# object_1_milling.net
KiCad netlist of a schematic drawn in EAGLE
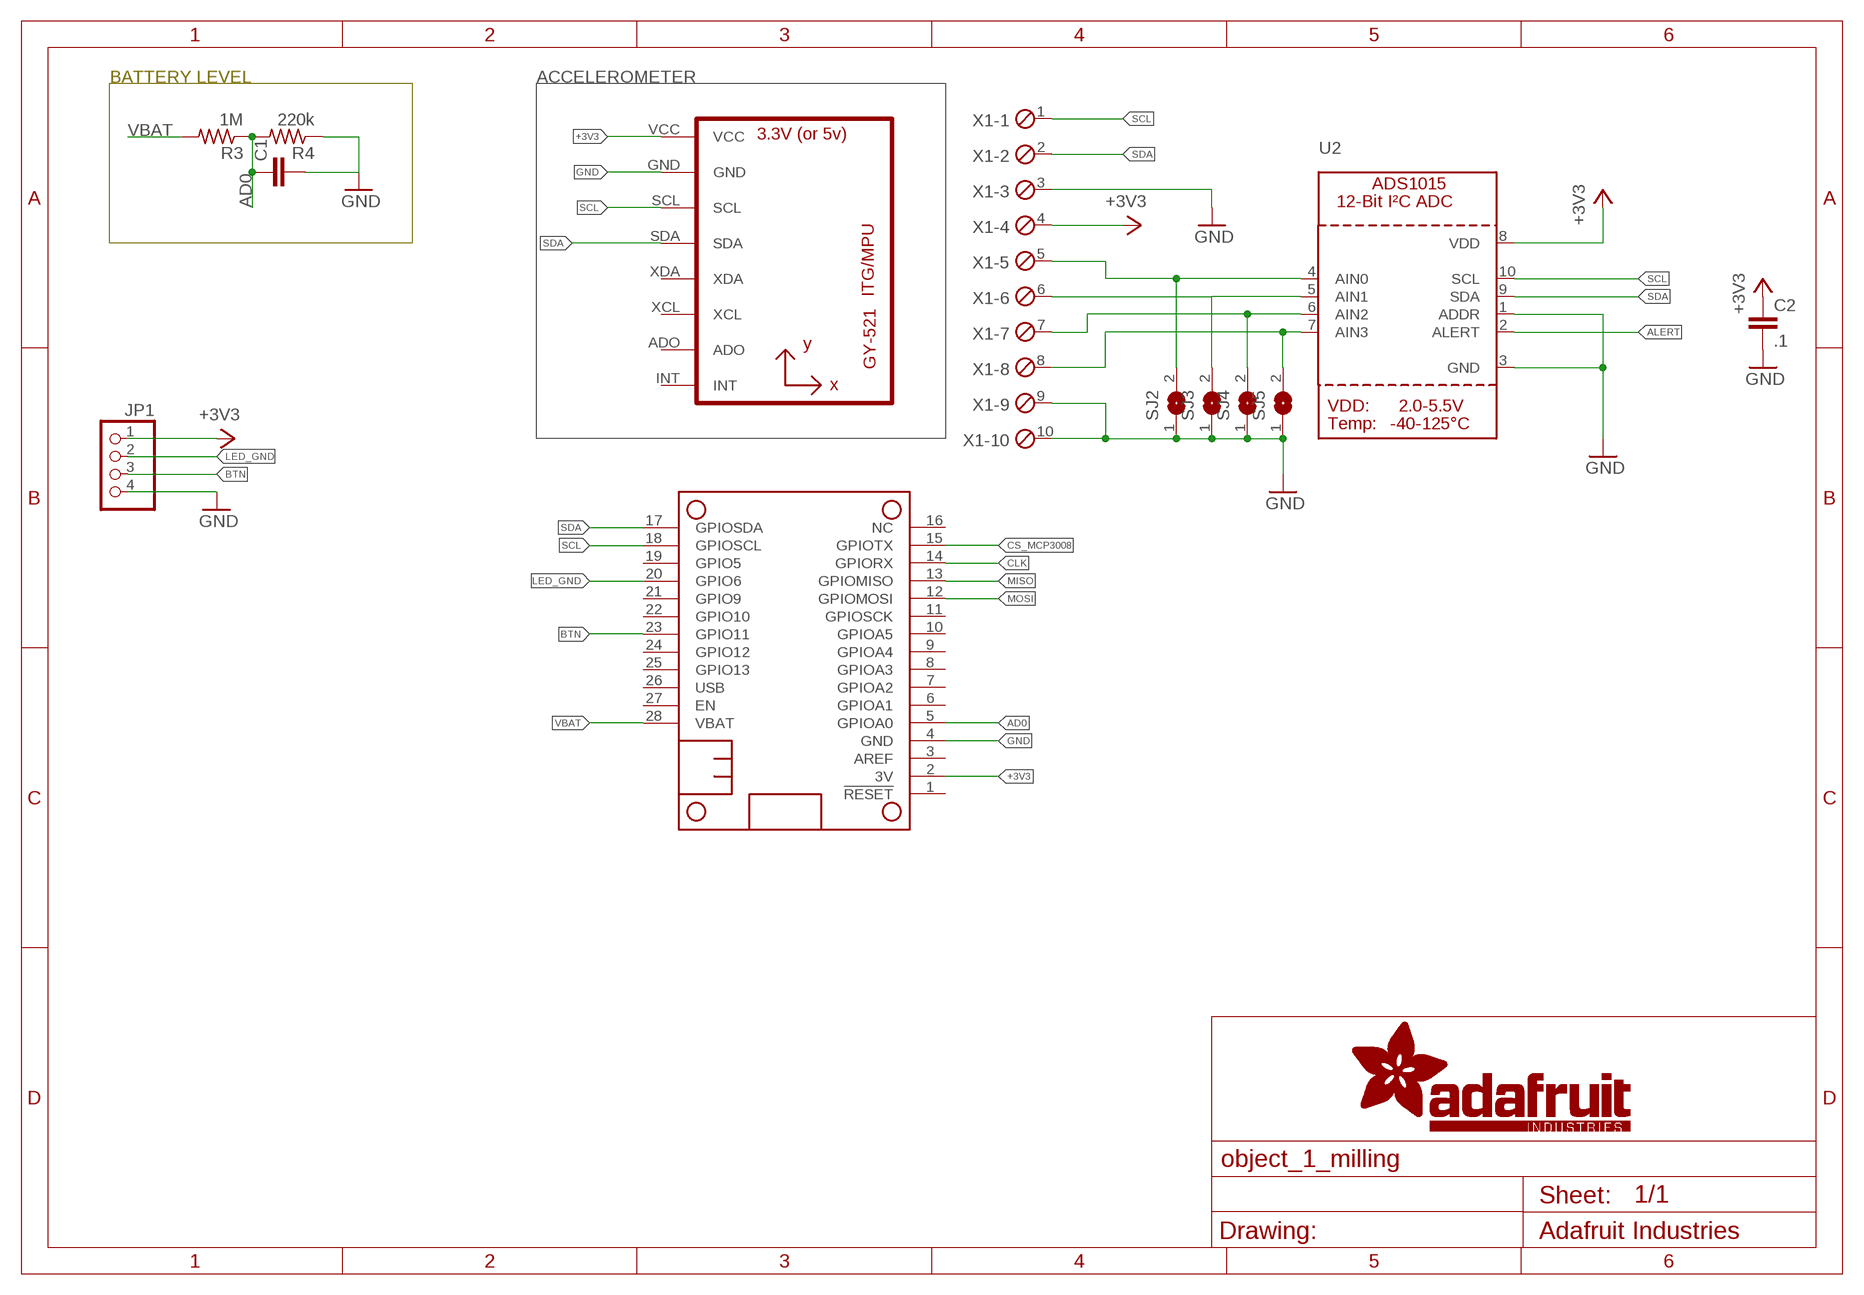
[diagram p0: schematic, sheet 1]

(export (version "E")
  (design (tool "Eeschema 10.0.6"))
  (components
    (comp (ref "C1")
      (value "C-EUC0805K")
      (footprint "eagle-import:C0805K")
      (libsource (lib "eagle-import") (part "C-EUC0805K"))
    )
    (comp (ref "C2")
      (value ".1")
      (footprint "eagle-import:C0805K")
      (libsource (lib "eagle-import") (part "C-EUC0805K"))
    )
    (comp (ref "JP1")
      (value "PINHD-1X4/90")
      (footprint "eagle-import:1X04_90")
      (libsource (lib "eagle-import") (part "PINHD-1X4/90"))
    )
    (comp (ref "MS1")
      (value "FEATHERWING_NODIM")
      (footprint "eagle-import:FEATHERWING_DIM")
      (libsource (lib "eagle-import") (part "FEATHERWING_NODIM"))
    )
    (comp (ref "R3")
      (value "1M")
      (footprint "eagle-import:M0805")
      (libsource (lib "eagle-import") (part "R-US_M0805"))
    )
    (comp (ref "R4")
      (value "220k")
      (footprint "eagle-import:M0805")
      (libsource (lib "eagle-import") (part "R-US_M0805"))
    )
    (comp (ref "SJ2")
      (value "SOLDERJUMPER")
      (footprint "eagle-import:SOLDERJUMPER_ARROW_NOPASTE")
      (libsource (lib "eagle-import") (part "SOLDERJUMPER"))
    )
    (comp (ref "SJ3")
      (value "SOLDERJUMPER")
      (footprint "eagle-import:SOLDERJUMPER_ARROW_NOPASTE")
      (libsource (lib "eagle-import") (part "SOLDERJUMPER"))
    )
    (comp (ref "SJ4")
      (value "SOLDERJUMPER")
      (footprint "eagle-import:SOLDERJUMPER_ARROW_NOPASTE")
      (libsource (lib "eagle-import") (part "SOLDERJUMPER"))
    )
    (comp (ref "SJ5")
      (value "SOLDERJUMPER")
      (footprint "eagle-import:SOLDERJUMPER_ARROW_NOPASTE")
      (libsource (lib "eagle-import") (part "SOLDERJUMPER"))
    )
    (comp (ref "U1")
      (value "GY-521MPU6050")
      (footprint "eagle-import:GY-521")
      (libsource (lib "eagle-import") (part "GY-521MPU6050"))
    )
    (comp (ref "U2")
      (value "ADC_ADS1015")
      (footprint "eagle-import:MSOP10")
      (libsource (lib "eagle-import") (part "ADC_ADS1015"))
    )
    (comp (ref "X1")
      (value "MPT10")
      (footprint "eagle-import:10POL254")
      (libsource (lib "eagle-import") (part "MPT10"))
    )
  )
  (nets
    (net (code "1") (name "+3V3") (class "Default")
      (node (ref "C2") (pin "1") (pinfunction "1_1") (pintype "passive"))
      (node (ref "JP1") (pin "1") (pinfunction "1_1") (pintype "passive"))
      (node (ref "MS1") (pin "2") (pinfunction "3V_2") (pintype "power_in"))
      (node (ref "U1") (pin "VCC") (pinfunction "VCC_VCC") (pintype "bidirectional"))
      (node (ref "U2") (pin "8") (pinfunction "VDD_8") (pintype "bidirectional"))
      (node (ref "X1") (pin "4") (pinfunction "1_4") (pintype "passive"))
    )
    (net (code "2") (name "/USB") (class "Default")
      (node (ref "MS1") (pin "26") (pinfunction "USB_26") (pintype "power_in"))
    )
    (net (code "3") (name "AD0") (class "Default")
      (node (ref "C1") (pin "1") (pinfunction "1_1") (pintype "passive"))
      (node (ref "MS1") (pin "5") (pinfunction "GPIOA0_5") (pintype "bidirectional"))
      (node (ref "R3") (pin "1") (pinfunction "1_1") (pintype "passive"))
      (node (ref "R4") (pin "2") (pinfunction "2_2") (pintype "passive"))
    )
    (net (code "4") (name "ALERT") (class "Default")
      (node (ref "U2") (pin "2") (pinfunction "ALERT_2") (pintype "bidirectional"))
    )
    (net (code "5") (name "BTN") (class "Default")
      (node (ref "JP1") (pin "3") (pinfunction "3_3") (pintype "passive"))
      (node (ref "MS1") (pin "23") (pinfunction "GPIO11_23") (pintype "bidirectional"))
    )
    (net (code "6") (name "CLK") (class "Default")
      (node (ref "MS1") (pin "14") (pinfunction "GPIORX_14") (pintype "bidirectional"))
    )
    (net (code "7") (name "CS_MCP3008") (class "Default")
      (node (ref "MS1") (pin "15") (pinfunction "GPIOTX_15") (pintype "bidirectional"))
    )
    (net (code "8") (name "GND") (class "Default")
      (node (ref "C1") (pin "2") (pinfunction "2_2") (pintype "passive"))
      (node (ref "C2") (pin "2") (pinfunction "2_2") (pintype "passive"))
      (node (ref "JP1") (pin "4") (pinfunction "4_4") (pintype "passive"))
      (node (ref "MS1") (pin "4") (pinfunction "GND_4") (pintype "power_in"))
      (node (ref "R4") (pin "1") (pinfunction "1_1") (pintype "passive"))
      (node (ref "SJ2") (pin "1") (pinfunction "1_1") (pintype "passive"))
      (node (ref "SJ3") (pin "1") (pinfunction "1_1") (pintype "passive"))
      (node (ref "SJ4") (pin "1") (pinfunction "1_1") (pintype "passive"))
      (node (ref "SJ5") (pin "1") (pinfunction "1_1") (pintype "passive"))
      (node (ref "U1") (pin "GND") (pinfunction "GND_GND") (pintype "bidirectional"))
      (node (ref "U2") (pin "1") (pinfunction "ADDR_1") (pintype "bidirectional"))
      (node (ref "U2") (pin "3") (pinfunction "GND_3") (pintype "bidirectional"))
      (node (ref "X1") (pin "10") (pinfunction "1_10") (pintype "passive"))
      (node (ref "X1") (pin "3") (pinfunction "1_3") (pintype "passive"))
      (node (ref "X1") (pin "9") (pinfunction "1_9") (pintype "passive"))
    )
    (net (code "9") (name "LED_GND") (class "Default")
      (node (ref "JP1") (pin "2") (pinfunction "2_2") (pintype "passive"))
      (node (ref "MS1") (pin "20") (pinfunction "GPIO6_20") (pintype "bidirectional"))
    )
    (net (code "10") (name "MISO") (class "Default")
      (node (ref "MS1") (pin "13") (pinfunction "GPIOMISO_13") (pintype "bidirectional"))
    )
    (net (code "11") (name "MOSI") (class "Default")
      (node (ref "MS1") (pin "12") (pinfunction "GPIOMOSI_12") (pintype "bidirectional"))
    )
    (net (code "12") (name "Net-(U2-AIN0)") (class "Default")
      (node (ref "SJ2") (pin "2") (pinfunction "2_2") (pintype "passive"))
      (node (ref "U2") (pin "4") (pinfunction "AIN0_4") (pintype "bidirectional"))
      (node (ref "X1") (pin "5") (pinfunction "1_5") (pintype "passive"))
    )
    (net (code "13") (name "Net-(U2-AIN1)") (class "Default")
      (node (ref "SJ3") (pin "2") (pinfunction "2_2") (pintype "passive"))
      (node (ref "U2") (pin "5") (pinfunction "AIN1_5") (pintype "bidirectional"))
      (node (ref "X1") (pin "6") (pinfunction "1_6") (pintype "passive"))
    )
    (net (code "14") (name "Net-(U2-AIN2)") (class "Default")
      (node (ref "SJ4") (pin "2") (pinfunction "2_2") (pintype "passive"))
      (node (ref "U2") (pin "6") (pinfunction "AIN2_6") (pintype "bidirectional"))
      (node (ref "X1") (pin "7") (pinfunction "1_7") (pintype "passive"))
    )
    (net (code "15") (name "Net-(U2-AIN3)") (class "Default")
      (node (ref "SJ5") (pin "2") (pinfunction "2_2") (pintype "passive"))
      (node (ref "U2") (pin "7") (pinfunction "AIN3_7") (pintype "bidirectional"))
      (node (ref "X1") (pin "8") (pinfunction "1_8") (pintype "passive"))
    )
    (net (code "16") (name "SCL") (class "Default")
      (node (ref "MS1") (pin "18") (pinfunction "GPIOSCL_18") (pintype "bidirectional"))
      (node (ref "U1") (pin "SCL") (pinfunction "SCL_SCL") (pintype "bidirectional"))
      (node (ref "U2") (pin "10") (pinfunction "SCL_10") (pintype "bidirectional"))
      (node (ref "X1") (pin "1") (pinfunction "1_1") (pintype "passive"))
    )
    (net (code "17") (name "SDA") (class "Default")
      (node (ref "MS1") (pin "17") (pinfunction "GPIOSDA_17") (pintype "bidirectional"))
      (node (ref "U1") (pin "SDA") (pinfunction "SDA_SDA") (pintype "bidirectional"))
      (node (ref "U2") (pin "9") (pinfunction "SDA_9") (pintype "bidirectional"))
      (node (ref "X1") (pin "2") (pinfunction "1_2") (pintype "passive"))
    )
    (net (code "18") (name "VBAT") (class "Default")
      (node (ref "MS1") (pin "28") (pinfunction "VBAT_28") (pintype "power_in"))
      (node (ref "R3") (pin "2") (pinfunction "2_2") (pintype "passive"))
    )
    (net (code "19") (name "unconnected-(MS1-AREF-Pad3)") (class "Default")
      (node (ref "MS1") (pin "3") (pinfunction "AREF_3") (pintype "passive"))
    )
    (net (code "20") (name "unconnected-(MS1-EN-Pad27)") (class "Default")
      (node (ref "MS1") (pin "27") (pinfunction "EN_27") (pintype "passive"))
    )
    (net (code "21") (name "unconnected-(MS1-GPIO5-Pad19)") (class "Default")
      (node (ref "MS1") (pin "19") (pinfunction "GPIO5_19") (pintype "bidirectional"))
    )
    (net (code "22") (name "unconnected-(MS1-GPIO9-Pad21)") (class "Default")
      (node (ref "MS1") (pin "21") (pinfunction "GPIO9_21") (pintype "bidirectional"))
    )
    (net (code "23") (name "unconnected-(MS1-GPIO10-Pad22)") (class "Default")
      (node (ref "MS1") (pin "22") (pinfunction "GPIO10_22") (pintype "bidirectional"))
    )
    (net (code "24") (name "unconnected-(MS1-GPIO12-Pad24)") (class "Default")
      (node (ref "MS1") (pin "24") (pinfunction "GPIO12_24") (pintype "bidirectional"))
    )
    (net (code "25") (name "unconnected-(MS1-GPIO13-Pad25)") (class "Default")
      (node (ref "MS1") (pin "25") (pinfunction "GPIO13_25") (pintype "bidirectional"))
    )
    (net (code "26") (name "unconnected-(MS1-GPIOA1-Pad6)") (class "Default")
      (node (ref "MS1") (pin "6") (pinfunction "GPIOA1_6") (pintype "bidirectional"))
    )
    (net (code "27") (name "unconnected-(MS1-GPIOA2-Pad7)") (class "Default")
      (node (ref "MS1") (pin "7") (pinfunction "GPIOA2_7") (pintype "bidirectional"))
    )
    (net (code "28") (name "unconnected-(MS1-GPIOA3-Pad8)") (class "Default")
      (node (ref "MS1") (pin "8") (pinfunction "GPIOA3_8") (pintype "bidirectional"))
    )
    (net (code "29") (name "unconnected-(MS1-GPIOA4-Pad9)") (class "Default")
      (node (ref "MS1") (pin "9") (pinfunction "GPIOA4_9") (pintype "bidirectional"))
    )
    (net (code "30") (name "unconnected-(MS1-GPIOA5-Pad10)") (class "Default")
      (node (ref "MS1") (pin "10") (pinfunction "GPIOA5_10") (pintype "bidirectional"))
    )
    (net (code "31") (name "unconnected-(MS1-GPIOSCK-Pad11)") (class "Default")
      (node (ref "MS1") (pin "11") (pinfunction "GPIOSCK_11") (pintype "bidirectional"))
    )
    (net (code "32") (name "unconnected-(MS1-NC-Pad16)") (class "Default")
      (node (ref "MS1") (pin "16") (pinfunction "NC_16") (pintype "passive"))
    )
    (net (code "33") (name "unconnected-(MS1-~{RESET}-Pad1)") (class "Default")
      (node (ref "MS1") (pin "1") (pinfunction "~{RESET}_1") (pintype "input"))
    )
    (net (code "34") (name "unconnected-(U1-PadADO)") (class "Default")
      (node (ref "U1") (pin "ADO") (pinfunction "ADO_ADO") (pintype "bidirectional"))
    )
    (net (code "35") (name "unconnected-(U1-PadINT)") (class "Default")
      (node (ref "U1") (pin "INT") (pinfunction "INT_INT") (pintype "bidirectional"))
    )
    (net (code "36") (name "unconnected-(U1-PadXCL)") (class "Default")
      (node (ref "U1") (pin "XCL") (pinfunction "XCL_XCL") (pintype "bidirectional"))
    )
    (net (code "37") (name "unconnected-(U1-PadXDA)") (class "Default")
      (node (ref "U1") (pin "XDA") (pinfunction "XDA_XDA") (pintype "bidirectional"))
    )
  )
)
